# 500_HEATERS.net
KiCad netlist of a schematic drawn in Altium Designer
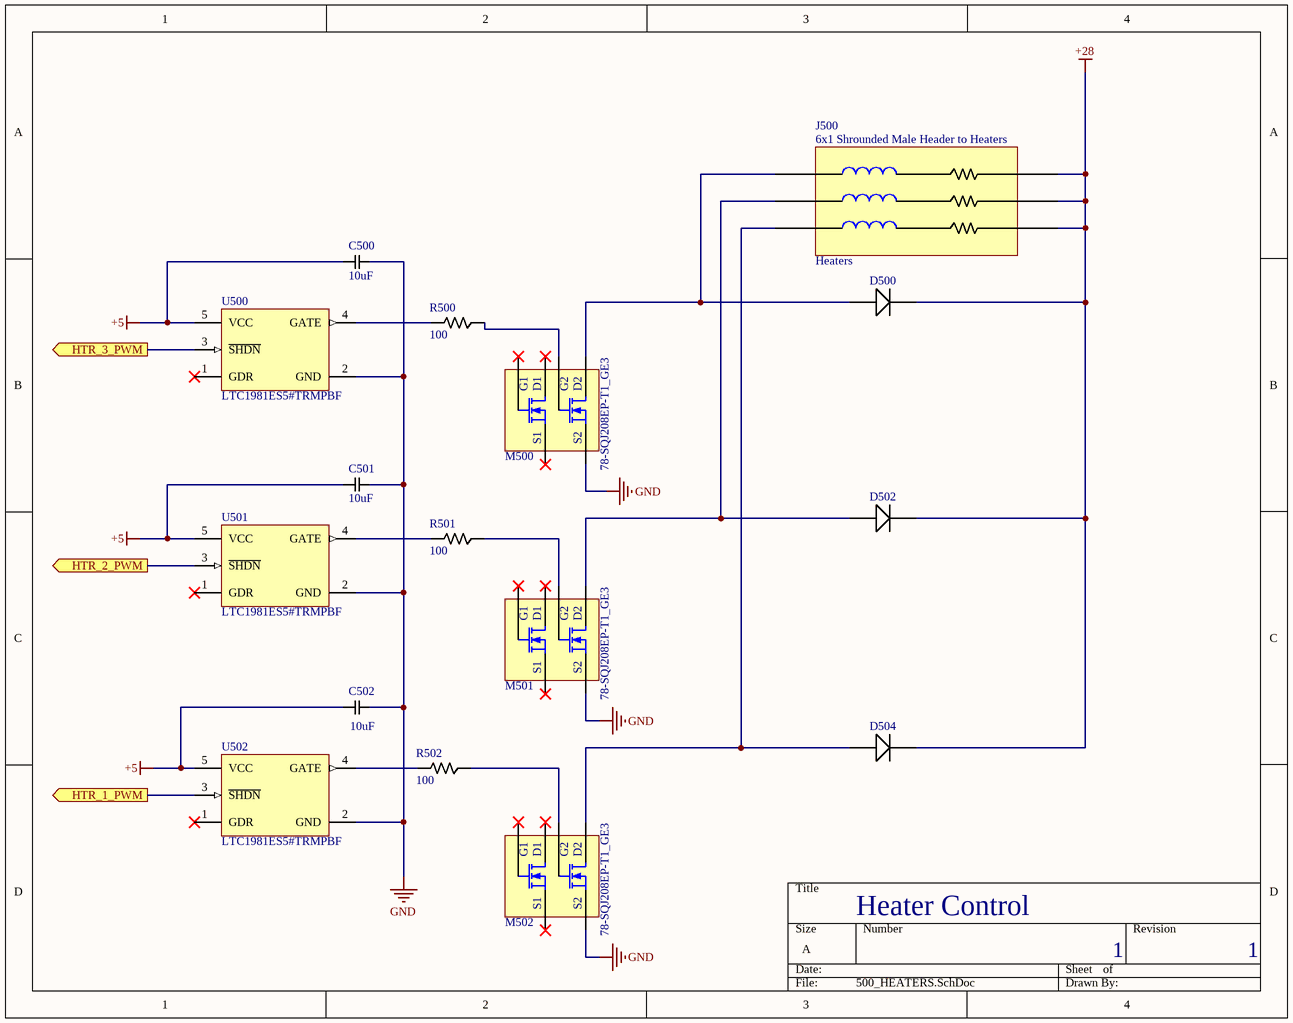
[diagram p0: 500_HEATERS.SchDoc]

(export (version "E")
  (design (tool "Eeschema 10.0.6"))
  (components
    (comp (ref "C500")
      (value "10uF")
      (footprint "IMPERIAL0805_CAPACITOR")
      (description "10 uF Capacitor")
      (fields (field (name "Comment") "10uF Capacitor"))
      (libsource (lib "OASIS_COMPONENTS_SYMBOLS") (part "C2012X8L1A106K125AE"))
    )
    (comp (ref "C501")
      (value "10uF")
      (footprint "IMPERIAL0805_CAPACITOR")
      (description "10 uF Capacitor")
      (fields (field (name "Comment") "10uF Capacitor"))
      (libsource (lib "OASIS_COMPONENTS_SYMBOLS") (part "C2012X8L1A106K125AE"))
    )
    (comp (ref "C502")
      (value "10uF")
      (footprint "IMPERIAL0805_CAPACITOR")
      (description "10 uF Capacitor")
      (fields (field (name "Comment") "10uF Capacitor"))
      (libsource (lib "OASIS_COMPONENTS_SYMBOLS") (part "C2012X8L1A106K125AE"))
    )
    (comp (ref "D500")
      (value "STPS1L40ZF")
      (footprint "*SODFL3718X108N")
      (description "1A Schottky Diode")
      (libsource (lib "OASIS_COMPONENTS_SYMBOLS") (part "STPS1L40ZF"))
    )
    (comp (ref "D502")
      (value "STPS1L40ZF")
      (footprint "*SODFL3718X108N")
      (description "1A Schottky Diode")
      (libsource (lib "OASIS_COMPONENTS_SYMBOLS") (part "STPS1L40ZF"))
    )
    (comp (ref "D504")
      (value "STPS1L40ZF")
      (footprint "*SODFL3718X108N")
      (description "1A Schottky Diode")
      (libsource (lib "OASIS_COMPONENTS_SYMBOLS") (part "STPS1L40ZF"))
    )
    (comp (ref "J500")
      (value "HeaterConnector")
      (footprint "MOLEX 6x1 latch header")
      (description "Symbolic schematic symbol showing the inductance and resitance of the heaters")
      (libsource (lib "OASIS_COMPONENTS_SYMBOLS") (part "HeaterConnector"))
    )
    (comp (ref "M500")
      (value "NPN MOSFET")
      (footprint "PowerPAK SO-8L DUAL ASYMMETRIC")
      (description "Two NPN Power Transistors for heater power control")
      (fields (field (name "SUPPLIER PART NUMBER 1") "78-SQJ208EP-T1_GE3"))
      (libsource (lib "OASIS_COMPONENTS_SYMBOLS") (part "SQJ208EP-T1_GE3"))
    )
    (comp (ref "M501")
      (value "NPN MOSFET")
      (footprint "PowerPAK SO-8L DUAL ASYMMETRIC")
      (description "Two NPN Power Transistors for heater power control")
      (fields (field (name "SUPPLIER PART NUMBER 1") "78-SQJ208EP-T1_GE3"))
      (libsource (lib "OASIS_COMPONENTS_SYMBOLS") (part "SQJ208EP-T1_GE3"))
    )
    (comp (ref "M502")
      (value "NPN MOSFET")
      (footprint "PowerPAK SO-8L DUAL ASYMMETRIC")
      (description "Two NPN Power Transistors for heater power control")
      (fields (field (name "SUPPLIER PART NUMBER 1") "78-SQJ208EP-T1_GE3"))
      (libsource (lib "OASIS_COMPONENTS_SYMBOLS") (part "SQJ208EP-T1_GE3"))
    )
    (comp (ref "R500")
      (value "100")
      (footprint "Imperial0603_RES")
      (description "100 Ohm Resistor")
      (fields (field (name "Comment") "CRCW0603100RFKEAC"))
      (libsource (lib "OASIS_COMPONENTS_SYMBOLS") (part "CRCW0603100RFKEAC"))
    )
    (comp (ref "R501")
      (value "100")
      (footprint "Imperial0603_RES")
      (description "100 Ohm Resistor")
      (fields (field (name "Comment") "CRCW0603100RFKEAC"))
      (libsource (lib "OASIS_COMPONENTS_SYMBOLS") (part "CRCW0603100RFKEAC"))
    )
    (comp (ref "R502")
      (value "100")
      (footprint "Imperial0603_RES")
      (description "100 Ohm Resistor")
      (fields (field (name "Comment") "CRCW0603100RFKEAC"))
      (libsource (lib "OASIS_COMPONENTS_SYMBOLS") (part "CRCW0603100RFKEAC"))
    )
    (comp (ref "U500")
      (value "LTC1981ES5#TRMPBF")
      (footprint "LT-S5-5-SOT-23_M")
      (fields (field (name "MANUFACTURER") "Analog Devices / Linear Technology"))
      (libsource (lib "OASIS_COMPONENTS_SYMBOLS") (part "CMP-0479-00408-1"))
    )
    (comp (ref "U501")
      (value "LTC1981ES5#TRMPBF")
      (footprint "LT-S5-5-SOT-23_M")
      (fields (field (name "MANUFACTURER") "Analog Devices / Linear Technology"))
      (libsource (lib "OASIS_COMPONENTS_SYMBOLS") (part "CMP-0479-00408-1"))
    )
    (comp (ref "U502")
      (value "LTC1981ES5#TRMPBF")
      (footprint "LT-S5-5-SOT-23_M")
      (fields (field (name "MANUFACTURER") "Analog Devices / Linear Technology"))
      (libsource (lib "OASIS_COMPONENTS_SYMBOLS") (part "CMP-0479-00408-1"))
    )
  )
  (nets
    (net (code "1") (name "+5") (class "Default")
      (node (ref "C500") (pin "2") (pinfunction "2_2") (pintype "passive"))
      (node (ref "C501") (pin "2") (pinfunction "2_2") (pintype "passive"))
      (node (ref "C502") (pin "2") (pinfunction "2_2") (pintype "passive"))
      (node (ref "U500") (pin "5") (pinfunction "VCC_5") (pintype "power_in"))
      (node (ref "U501") (pin "5") (pinfunction "VCC_5") (pintype "power_in"))
      (node (ref "U502") (pin "5") (pinfunction "VCC_5") (pintype "power_in"))
    )
    (net (code "2") (name "+28") (class "Default")
      (node (ref "D500") (pin "1") (pinfunction "cathode_1") (pintype "passive"))
      (node (ref "D502") (pin "1") (pinfunction "cathode_1") (pintype "passive"))
      (node (ref "D504") (pin "1") (pinfunction "cathode_1") (pintype "passive"))
      (node (ref "J500") (pin "2") (pinfunction "2_2") (pintype "passive"))
      (node (ref "J500") (pin "4") (pinfunction "4_4") (pintype "passive"))
      (node (ref "J500") (pin "6") (pinfunction "6_6") (pintype "passive"))
    )
    (net (code "3") (name "/HTR_1_PWM") (class "Default")
      (node (ref "U502") (pin "3") (pinfunction "~{SHDN}_3") (pintype "input"))
    )
    (net (code "4") (name "/HTR_2_PWM") (class "Default")
      (node (ref "U501") (pin "3") (pinfunction "~{SHDN}_3") (pintype "input"))
    )
    (net (code "5") (name "/HTR_3_PWM") (class "Default")
      (node (ref "U500") (pin "3") (pinfunction "~{SHDN}_3") (pintype "input"))
    )
    (net (code "6") (name "GND") (class "Default")
      (node (ref "C500") (pin "1") (pinfunction "1_1") (pintype "passive"))
      (node (ref "C501") (pin "1") (pinfunction "1_1") (pintype "passive"))
      (node (ref "C502") (pin "1") (pinfunction "1_1") (pintype "passive"))
      (node (ref "M500") (pin "S2") (pinfunction "S2_S2") (pintype "passive"))
      (node (ref "M501") (pin "S2") (pinfunction "S2_S2") (pintype "passive"))
      (node (ref "M502") (pin "S2") (pinfunction "S2_S2") (pintype "passive"))
      (node (ref "U500") (pin "2") (pinfunction "GND_2") (pintype "power_in"))
      (node (ref "U501") (pin "2") (pinfunction "GND_2") (pintype "power_in"))
      (node (ref "U502") (pin "2") (pinfunction "GND_2") (pintype "power_in"))
    )
    (net (code "7") (name "Net-(D500-anode)") (class "Default")
      (node (ref "D500") (pin "2") (pinfunction "anode_2") (pintype "passive"))
      (node (ref "J500") (pin "1") (pinfunction "1_1") (pintype "passive"))
      (node (ref "M500") (pin "D2") (pinfunction "D2_D2") (pintype "passive"))
    )
    (net (code "8") (name "Net-(D502-anode)") (class "Default")
      (node (ref "D502") (pin "2") (pinfunction "anode_2") (pintype "passive"))
      (node (ref "J500") (pin "3") (pinfunction "3_3") (pintype "passive"))
      (node (ref "M501") (pin "D2") (pinfunction "D2_D2") (pintype "passive"))
    )
    (net (code "9") (name "Net-(D504-anode)") (class "Default")
      (node (ref "D504") (pin "2") (pinfunction "anode_2") (pintype "passive"))
      (node (ref "J500") (pin "5") (pinfunction "5_5") (pintype "passive"))
      (node (ref "M502") (pin "D2") (pinfunction "D2_D2") (pintype "passive"))
    )
    (net (code "10") (name "Net-(M500-PadG2)") (class "Default")
      (node (ref "M500") (pin "G2") (pinfunction "G2_G2") (pintype "passive"))
      (node (ref "R500") (pin "2") (pinfunction "2_2") (pintype "passive"))
    )
    (net (code "11") (name "Net-(M501-PadG2)") (class "Default")
      (node (ref "M501") (pin "G2") (pinfunction "G2_G2") (pintype "passive"))
      (node (ref "R501") (pin "2") (pinfunction "2_2") (pintype "passive"))
    )
    (net (code "12") (name "Net-(M502-PadG2)") (class "Default")
      (node (ref "M502") (pin "G2") (pinfunction "G2_G2") (pintype "passive"))
      (node (ref "R502") (pin "2") (pinfunction "2_2") (pintype "passive"))
    )
    (net (code "13") (name "Net-(U500-GATE)") (class "Default")
      (node (ref "R500") (pin "1") (pinfunction "1_1") (pintype "passive"))
      (node (ref "U500") (pin "4") (pinfunction "GATE_4") (pintype "output"))
    )
    (net (code "14") (name "Net-(U501-GATE)") (class "Default")
      (node (ref "R501") (pin "1") (pinfunction "1_1") (pintype "passive"))
      (node (ref "U501") (pin "4") (pinfunction "GATE_4") (pintype "output"))
    )
    (net (code "15") (name "Net-(U502-GATE)") (class "Default")
      (node (ref "R502") (pin "1") (pinfunction "1_1") (pintype "passive"))
      (node (ref "U502") (pin "4") (pinfunction "GATE_4") (pintype "output"))
    )
    (net (code "16") (name "unconnected-(M500-PadD1)") (class "Default")
      (node (ref "M500") (pin "D1") (pinfunction "D1_D1") (pintype "passive+no_connect"))
    )
    (net (code "17") (name "unconnected-(M500-PadG1)") (class "Default")
      (node (ref "M500") (pin "G1") (pinfunction "G1_G1") (pintype "passive+no_connect"))
    )
    (net (code "18") (name "unconnected-(M500-PadS1)") (class "Default")
      (node (ref "M500") (pin "S1") (pinfunction "S1_S1") (pintype "passive+no_connect"))
    )
    (net (code "19") (name "unconnected-(M501-PadD1)") (class "Default")
      (node (ref "M501") (pin "D1") (pinfunction "D1_D1") (pintype "passive+no_connect"))
    )
    (net (code "20") (name "unconnected-(M501-PadG1)") (class "Default")
      (node (ref "M501") (pin "G1") (pinfunction "G1_G1") (pintype "passive+no_connect"))
    )
    (net (code "21") (name "unconnected-(M501-PadS1)") (class "Default")
      (node (ref "M501") (pin "S1") (pinfunction "S1_S1") (pintype "passive+no_connect"))
    )
    (net (code "22") (name "unconnected-(M502-PadD1)") (class "Default")
      (node (ref "M502") (pin "D1") (pinfunction "D1_D1") (pintype "passive+no_connect"))
    )
    (net (code "23") (name "unconnected-(M502-PadG1)") (class "Default")
      (node (ref "M502") (pin "G1") (pinfunction "G1_G1") (pintype "passive+no_connect"))
    )
    (net (code "24") (name "unconnected-(M502-PadS1)") (class "Default")
      (node (ref "M502") (pin "S1") (pinfunction "S1_S1") (pintype "passive+no_connect"))
    )
    (net (code "25") (name "unconnected-(U500-GDR-Pad1)") (class "Default")
      (node (ref "U500") (pin "1") (pinfunction "GDR_1") (pintype "open_collector+no_connect"))
    )
    (net (code "26") (name "unconnected-(U501-GDR-Pad1)") (class "Default")
      (node (ref "U501") (pin "1") (pinfunction "GDR_1") (pintype "open_collector+no_connect"))
    )
    (net (code "27") (name "unconnected-(U502-GDR-Pad1)") (class "Default")
      (node (ref "U502") (pin "1") (pinfunction "GDR_1") (pintype "open_collector+no_connect"))
    )
  )
)
